# pmon_oled.net
KiCad netlist of a schematic drawn in EAGLE
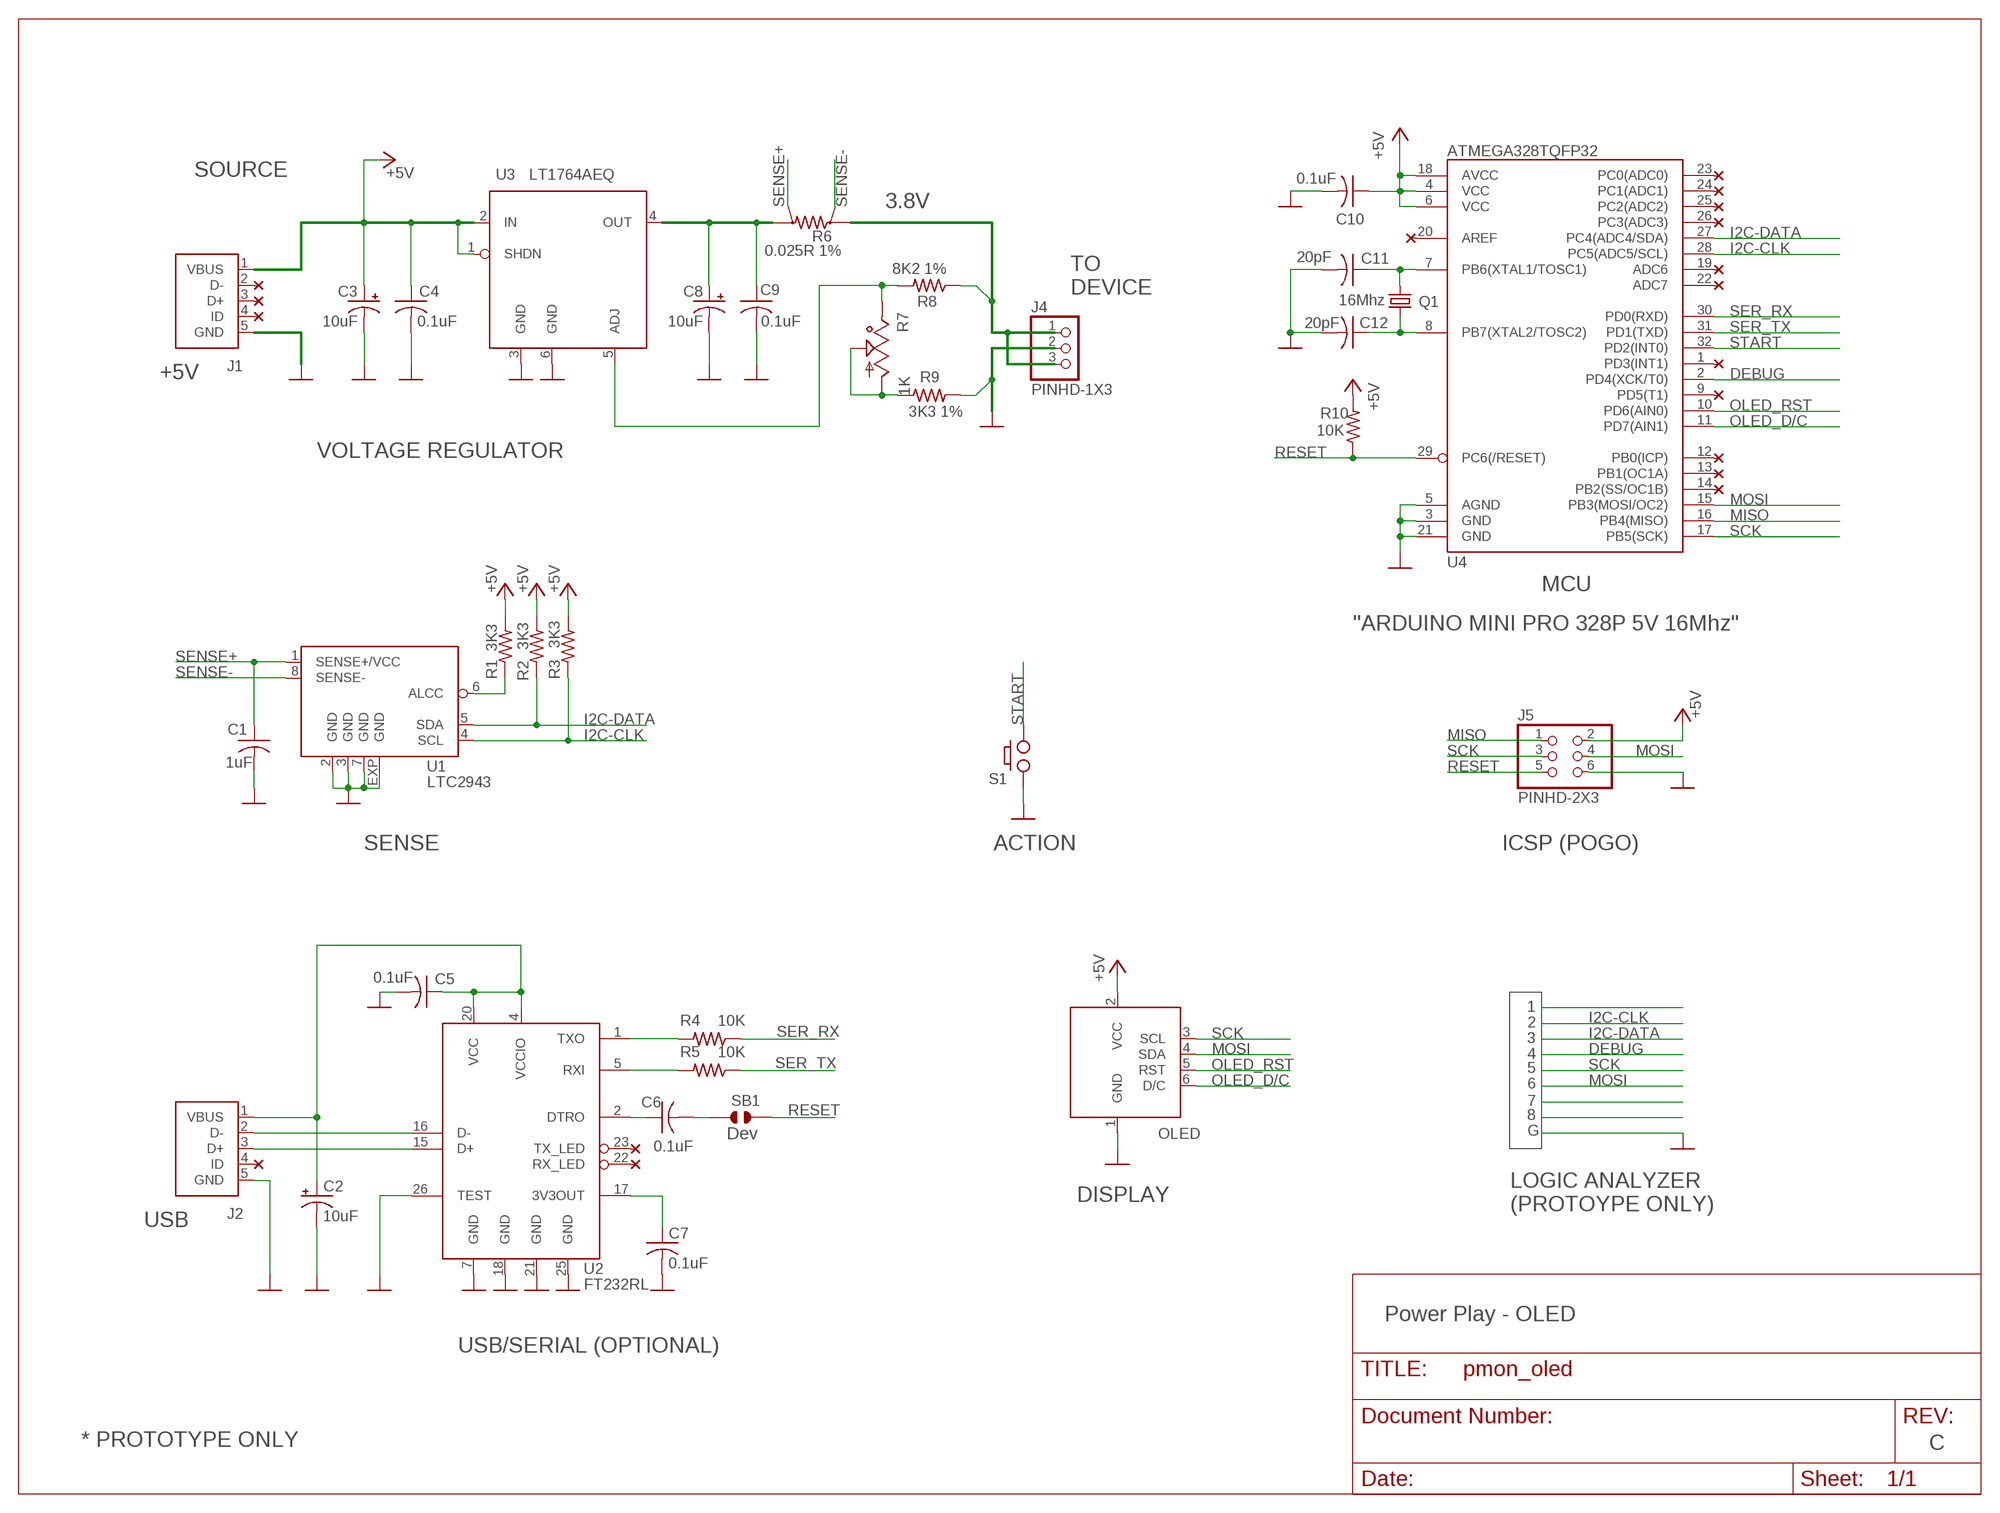
[diagram p0: schematic, sheet 1]

(export (version "E")
  (design (tool "Eeschema 10.0.6"))
  (components
    (comp (ref "C1")
      (value "1uF")
      (footprint "eagle-import:C0603")
      (libsource (lib "eagle-import") (part "CAP-C0603"))
    )
    (comp (ref "C2")
      (value "10uF")
      (footprint "eagle-import:A_3216-18R")
      (libsource (lib "eagle-import") (part "CPOL-USA/3216-18R"))
    )
    (comp (ref "C3")
      (value "10uF")
      (footprint "eagle-import:A_3216-18R")
      (libsource (lib "eagle-import") (part "CPOL-USA/3216-18R"))
    )
    (comp (ref "C4")
      (value "0.1uF")
      (footprint "eagle-import:C0603")
      (libsource (lib "eagle-import") (part "CAP-C0603"))
    )
    (comp (ref "C5")
      (value "0.1uF")
      (footprint "eagle-import:C0603")
      (libsource (lib "eagle-import") (part "CAP-C0603"))
    )
    (comp (ref "C6")
      (value "0.1uF")
      (footprint "eagle-import:C0603")
      (libsource (lib "eagle-import") (part "CAP-C0603"))
    )
    (comp (ref "C7")
      (value "0.1uF")
      (footprint "eagle-import:C0603")
      (libsource (lib "eagle-import") (part "CAP-C0603"))
    )
    (comp (ref "C8")
      (value "10uF")
      (footprint "eagle-import:A_3216-18R")
      (libsource (lib "eagle-import") (part "CPOL-USA/3216-18R"))
    )
    (comp (ref "C9")
      (value "0.1uF")
      (footprint "eagle-import:C0603")
      (libsource (lib "eagle-import") (part "CAP-C0603"))
    )
    (comp (ref "C10")
      (value "0.1uF")
      (footprint "eagle-import:C0603")
      (libsource (lib "eagle-import") (part "CAP-C0603"))
    )
    (comp (ref "C11")
      (value "20pF")
      (footprint "eagle-import:C0603")
      (libsource (lib "eagle-import") (part "CAP-C0603"))
    )
    (comp (ref "C12")
      (value "20pF")
      (footprint "eagle-import:C0603")
      (libsource (lib "eagle-import") (part "CAP-C0603"))
    )
    (comp (ref "J1")
      (value "USB")
      (footprint "eagle-import:USB-MICRO-ZX62RD-AB-5P8")
      (libsource (lib "eagle-import") (part "USB"))
    )
    (comp (ref "J2")
      (value "USB")
      (footprint "eagle-import:USB-MICRO-ZX62RD-AB-5P8")
      (libsource (lib "eagle-import") (part "USB"))
    )
    (comp (ref "J4")
      (value "PINHD-1X3")
      (footprint "eagle-import:1X03")
      (libsource (lib "eagle-import") (part "PINHD-1X3"))
    )
    (comp (ref "J5")
      (value "PINHD-2X3")
      (footprint "eagle-import:2X03")
      (libsource (lib "eagle-import") (part "PINHD-2X3"))
    )
    (comp (ref "OLED")
      (value "OLED")
      (footprint "eagle-import:OLED")
      (libsource (lib "eagle-import") (part "OLED"))
    )
    (comp (ref "Q1")
      (value "16Mhz")
      (footprint "eagle-import:CRYSTAL-CTS406")
      (libsource (lib "eagle-import") (part "CRYSTALCTS406"))
    )
    (comp (ref "R1")
      (value "3K3")
      (footprint "eagle-import:R0603")
      (libsource (lib "eagle-import") (part "RES-R0603"))
    )
    (comp (ref "R2")
      (value "3K3")
      (footprint "eagle-import:R0603")
      (libsource (lib "eagle-import") (part "RES-R0603"))
    )
    (comp (ref "R3")
      (value "3K3")
      (footprint "eagle-import:R0603")
      (libsource (lib "eagle-import") (part "RES-R0603"))
    )
    (comp (ref "R4")
      (value "10K")
      (footprint "eagle-import:R0603")
      (libsource (lib "eagle-import") (part "RES-R0603"))
    )
    (comp (ref "R5")
      (value "10K")
      (footprint "eagle-import:R0603")
      (libsource (lib "eagle-import") (part "RES-R0603"))
    )
    (comp (ref "R6")
      (value "0.025R 1%")
      (footprint "eagle-import:KELVIN-6432")
      (libsource (lib "eagle-import") (part "RES-SHUNT-6432"))
    )
    (comp (ref "R7")
      (value "1K")
      (footprint "eagle-import:TRIM-POT_SM-42_43A")
      (libsource (lib "eagle-import") (part "TRIM_US-SM-42/43A"))
    )
    (comp (ref "R8")
      (value "8K2 1%")
      (footprint "eagle-import:R0603")
      (libsource (lib "eagle-import") (part "RES-R0603"))
    )
    (comp (ref "R9")
      (value "3K3 1%")
      (footprint "eagle-import:R0603")
      (libsource (lib "eagle-import") (part "RES-R0603"))
    )
    (comp (ref "R10")
      (value "10K")
      (footprint "eagle-import:R0603")
      (libsource (lib "eagle-import") (part "RES-R0603"))
    )
    (comp (ref "S1")
      (value "PUSH_BUTTON")
      (footprint "eagle-import:TLE1105")
      (libsource (lib "eagle-import") (part "PUSH_BUTTON"))
    )
    (comp (ref "SB1")
      (value "JUMPER_SOLDER_1X2")
      (footprint "eagle-import:JUMPER_SOLDER_1X2")
      (libsource (lib "eagle-import") (part "JUMPER_SOLDER_1X2"))
    )
    (comp (ref "U1")
      (value "LTC2943")
      (footprint "eagle-import:DFN8-3X3")
      (libsource (lib "eagle-import") (part "LTC2943"))
    )
    (comp (ref "U2")
      (value "FT232RL")
      (footprint "eagle-import:SSOP28DB")
      (libsource (lib "eagle-import") (part "FT232RL"))
    )
    (comp (ref "U3")
      (value "LT1764AEQ")
      (footprint "eagle-import:TO263-5")
      (libsource (lib "eagle-import") (part "LTE1764"))
    )
    (comp (ref "U4")
      (value "ATMEGA328TQFP32")
      (footprint "eagle-import:TQFP32-08")
      (libsource (lib "eagle-import") (part "ATMEGA328TQFP32"))
    )
  )
  (nets
    (net (code "1") (name "+5V") (class "Default")
      (node (ref "C10") (pin "1") (pinfunction "1_1") (pintype "passive"))
      (node (ref "C3") (pin "+") (pinfunction "+_+") (pintype "passive"))
      (node (ref "C4") (pin "1") (pinfunction "1_1") (pintype "passive"))
      (node (ref "J1") (pin "1") (pinfunction "VBUS_1") (pintype "bidirectional"))
      (node (ref "J5") (pin "2") (pinfunction "2_2") (pintype "passive"))
      (node (ref "OLED") (pin "2") (pinfunction "VCC_2") (pintype "power_in"))
      (node (ref "R1") (pin "2") (pinfunction "2_2") (pintype "passive"))
      (node (ref "R10") (pin "2") (pinfunction "2_2") (pintype "passive"))
      (node (ref "R2") (pin "2") (pinfunction "2_2") (pintype "passive"))
      (node (ref "R3") (pin "2") (pinfunction "2_2") (pintype "passive"))
      (node (ref "U3") (pin "1") (pinfunction "SHDN_1") (pintype "bidirectional"))
      (node (ref "U3") (pin "2") (pinfunction "IN_2") (pintype "bidirectional"))
      (node (ref "U4") (pin "18") (pinfunction "AVCC_18") (pintype "power_in"))
      (node (ref "U4") (pin "4") (pinfunction "VCC_4") (pintype "power_in"))
      (node (ref "U4") (pin "6") (pinfunction "VCC_6") (pintype "power_in"))
    )
    (net (code "2") (name "/AREF") (class "Default")
      (node (ref "U4") (pin "20") (pinfunction "AREF_20") (pintype "power_in"))
    )
    (net (code "3") (name "/DEBUG") (class "Default")
      (node (ref "U4") (pin "2") (pinfunction "PD4(XCK/T0)_2") (pintype "bidirectional"))
    )
    (net (code "4") (name "/I2C-CLK") (class "Default")
      (node (ref "R3") (pin "1") (pinfunction "1_1") (pintype "passive"))
      (node (ref "U1") (pin "4") (pinfunction "SCL_4") (pintype "input"))
      (node (ref "U4") (pin "28") (pinfunction "PC5(ADC5/SCL)_28") (pintype "bidirectional"))
    )
    (net (code "5") (name "/I2C-DATA") (class "Default")
      (node (ref "R2") (pin "1") (pinfunction "1_1") (pintype "passive"))
      (node (ref "U1") (pin "5") (pinfunction "SDA_5") (pintype "bidirectional"))
      (node (ref "U4") (pin "27") (pinfunction "PC4(ADC4/SDA)_27") (pintype "bidirectional"))
    )
    (net (code "6") (name "/MISO") (class "Default")
      (node (ref "J5") (pin "1") (pinfunction "1_1") (pintype "passive"))
      (node (ref "U4") (pin "16") (pinfunction "PB4(MISO)_16") (pintype "bidirectional"))
    )
    (net (code "7") (name "/MOSI") (class "Default")
      (node (ref "J5") (pin "4") (pinfunction "4_4") (pintype "passive"))
      (node (ref "OLED") (pin "4") (pinfunction "SDA_4") (pintype "input"))
      (node (ref "U4") (pin "15") (pinfunction "PB3(MOSI/OC2)_15") (pintype "bidirectional"))
    )
    (net (code "8") (name "/OLED_D{slash}C") (class "Default")
      (node (ref "OLED") (pin "6") (pinfunction "D/C_6") (pintype "input"))
      (node (ref "U4") (pin "11") (pinfunction "PD7(AIN1)_11") (pintype "bidirectional"))
    )
    (net (code "9") (name "/OLED_RST") (class "Default")
      (node (ref "OLED") (pin "5") (pinfunction "RST_5") (pintype "input"))
      (node (ref "U4") (pin "10") (pinfunction "PD6(AIN0)_10") (pintype "bidirectional"))
    )
    (net (code "10") (name "/RESET") (class "Default")
      (node (ref "J5") (pin "5") (pinfunction "5_5") (pintype "passive"))
      (node (ref "R10") (pin "1") (pinfunction "1_1") (pintype "passive"))
      (node (ref "SB1") (pin "2") (pinfunction "2_2") (pintype "passive"))
      (node (ref "U4") (pin "29") (pinfunction "PC6(/RESET)_29") (pintype "bidirectional"))
    )
    (net (code "11") (name "/SCK") (class "Default")
      (node (ref "J5") (pin "3") (pinfunction "3_3") (pintype "passive"))
      (node (ref "OLED") (pin "3") (pinfunction "SCL_3") (pintype "input"))
      (node (ref "U4") (pin "17") (pinfunction "PB5(SCK)_17") (pintype "bidirectional"))
    )
    (net (code "12") (name "/SENSE+") (class "Default")
      (node (ref "C1") (pin "1") (pinfunction "1_1") (pintype "passive"))
      (node (ref "R6") (pin "V2") (pinfunction "V2_V2") (pintype "passive"))
      (node (ref "U1") (pin "1") (pinfunction "SENSE+/VCC_1") (pintype "passive"))
    )
    (net (code "13") (name "/SENSE-") (class "Default")
      (node (ref "R6") (pin "V1") (pinfunction "V1_V1") (pintype "passive"))
      (node (ref "U1") (pin "8") (pinfunction "SENSE-_8") (pintype "passive"))
    )
    (net (code "14") (name "/SER_RX") (class "Default")
      (node (ref "R4") (pin "1") (pinfunction "1_1") (pintype "passive"))
      (node (ref "U4") (pin "30") (pinfunction "PD0(RXD)_30") (pintype "bidirectional"))
    )
    (net (code "15") (name "/SER_TX") (class "Default")
      (node (ref "R5") (pin "1") (pinfunction "1_1") (pintype "passive"))
      (node (ref "U4") (pin "31") (pinfunction "PD1(TXD)_31") (pintype "bidirectional"))
    )
    (net (code "16") (name "/START") (class "Default")
      (node (ref "S1") (pin "B") (pinfunction "2_B") (pintype "passive"))
      (node (ref "U4") (pin "32") (pinfunction "PD2(INT0)_32") (pintype "bidirectional"))
    )
    (net (code "17") (name "GND") (class "Default")
      (node (ref "C1") (pin "2") (pinfunction "2_2") (pintype "passive"))
      (node (ref "C10") (pin "2") (pinfunction "2_2") (pintype "passive"))
      (node (ref "C11") (pin "2") (pinfunction "2_2") (pintype "passive"))
      (node (ref "C12") (pin "2") (pinfunction "2_2") (pintype "passive"))
      (node (ref "C2") (pin "-") (pinfunction "-_-") (pintype "passive"))
      (node (ref "C3") (pin "-") (pinfunction "-_-") (pintype "passive"))
      (node (ref "C4") (pin "2") (pinfunction "2_2") (pintype "passive"))
      (node (ref "C5") (pin "2") (pinfunction "2_2") (pintype "passive"))
      (node (ref "C7") (pin "2") (pinfunction "2_2") (pintype "passive"))
      (node (ref "C8") (pin "-") (pinfunction "-_-") (pintype "passive"))
      (node (ref "C9") (pin "2") (pinfunction "2_2") (pintype "passive"))
      (node (ref "J1") (pin "5") (pinfunction "GND_5") (pintype "bidirectional"))
      (node (ref "J2") (pin "5") (pinfunction "GND_5") (pintype "bidirectional"))
      (node (ref "J4") (pin "2") (pinfunction "2_2") (pintype "passive"))
      (node (ref "J5") (pin "6") (pinfunction "6_6") (pintype "passive"))
      (node (ref "OLED") (pin "1") (pinfunction "GND_1") (pintype "power_in"))
      (node (ref "R9") (pin "2") (pinfunction "2_2") (pintype "passive"))
      (node (ref "S1") (pin "A") (pinfunction "1_A") (pintype "passive"))
      (node (ref "U1") (pin "2") (pinfunction "GND_2") (pintype "power_in"))
      (node (ref "U1") (pin "3") (pinfunction "GND_3") (pintype "power_in"))
      (node (ref "U1") (pin "7") (pinfunction "GND_7") (pintype "power_in"))
      (node (ref "U1") (pin "EXP") (pinfunction "GND_EXP") (pintype "power_in"))
      (node (ref "U2") (pin "18") (pinfunction "GND_18") (pintype "power_in"))
      (node (ref "U2") (pin "21") (pinfunction "GND_21") (pintype "power_in"))
      (node (ref "U2") (pin "25") (pinfunction "GND_25") (pintype "power_in"))
      (node (ref "U2") (pin "26") (pinfunction "TEST_26") (pintype "input"))
      (node (ref "U2") (pin "7") (pinfunction "GND_7") (pintype "power_in"))
      (node (ref "U3") (pin "3") (pinfunction "GND_3") (pintype "bidirectional"))
      (node (ref "U3") (pin "6") (pinfunction "GND_6") (pintype "bidirectional"))
      (node (ref "U4") (pin "21") (pinfunction "GND_21") (pintype "power_in"))
      (node (ref "U4") (pin "3") (pinfunction "GND_3") (pintype "power_in"))
      (node (ref "U4") (pin "5") (pinfunction "AGND_5") (pintype "power_in"))
    )
    (net (code "18") (name "Net-(C6-Pad2)") (class "Default")
      (node (ref "C6") (pin "2") (pinfunction "2_2") (pintype "passive"))
      (node (ref "SB1") (pin "1") (pinfunction "1_1") (pintype "passive"))
    )
    (net (code "19") (name "Net-(J2-D+)") (class "Default")
      (node (ref "J2") (pin "3") (pinfunction "D+_3") (pintype "bidirectional"))
      (node (ref "U2") (pin "15") (pinfunction "D+_15") (pintype "passive"))
    )
    (net (code "20") (name "Net-(J2-D-)") (class "Default")
      (node (ref "J2") (pin "2") (pinfunction "D-_2") (pintype "bidirectional"))
      (node (ref "U2") (pin "16") (pinfunction "D-_16") (pintype "passive"))
    )
    (net (code "21") (name "Net-(J2-VBUS)") (class "Default")
      (node (ref "C2") (pin "+") (pinfunction "+_+") (pintype "passive"))
      (node (ref "C5") (pin "1") (pinfunction "1_1") (pintype "passive"))
      (node (ref "J2") (pin "1") (pinfunction "VBUS_1") (pintype "bidirectional"))
      (node (ref "U2") (pin "20") (pinfunction "VCC_20") (pintype "power_in"))
      (node (ref "U2") (pin "4") (pinfunction "VCCIO_4") (pintype "power_in"))
    )
    (net (code "22") (name "Net-(J4-Pad1)") (class "Default")
      (node (ref "J4") (pin "1") (pinfunction "1_1") (pintype "passive"))
      (node (ref "J4") (pin "3") (pinfunction "3_3") (pintype "passive"))
      (node (ref "R6") (pin "I1") (pinfunction "I1_I1") (pintype "passive"))
      (node (ref "R8") (pin "1") (pinfunction "1_1") (pintype "passive"))
    )
    (net (code "23") (name "Net-(Q1-2)") (class "Default")
      (node (ref "C12") (pin "1") (pinfunction "1_1") (pintype "passive"))
      (node (ref "Q1") (pin "3") (pinfunction "2_3") (pintype "passive"))
      (node (ref "U4") (pin "8") (pinfunction "PB7(XTAL2/TOSC2)_8") (pintype "bidirectional"))
    )
    (net (code "24") (name "Net-(R7-Pad1)") (class "Default")
      (node (ref "R7") (pin "1") (pinfunction "1_1") (pintype "passive"))
      (node (ref "R7") (pin "2") (pinfunction "2_2") (pintype "passive"))
      (node (ref "R9") (pin "1") (pinfunction "1_1") (pintype "passive"))
    )
    (net (code "25") (name "Net-(U1-ALCC)") (class "Default")
      (node (ref "R1") (pin "1") (pinfunction "1_1") (pintype "passive"))
      (node (ref "U1") (pin "6") (pinfunction "ALCC_6") (pintype "open_collector"))
    )
    (net (code "26") (name "Net-(U2-3V3OUT)") (class "Default")
      (node (ref "C7") (pin "1") (pinfunction "1_1") (pintype "passive"))
      (node (ref "U2") (pin "17") (pinfunction "3V3OUT_17") (pintype "power_in"))
    )
    (net (code "27") (name "Net-(U2-DTRO)") (class "Default")
      (node (ref "C6") (pin "1") (pinfunction "1_1") (pintype "passive"))
      (node (ref "U2") (pin "2") (pinfunction "DTRO_2") (pintype "output"))
    )
    (net (code "28") (name "Net-(U2-RXI)") (class "Default")
      (node (ref "R5") (pin "2") (pinfunction "2_2") (pintype "passive"))
      (node (ref "U2") (pin "5") (pinfunction "RXI_5") (pintype "input"))
    )
    (net (code "29") (name "Net-(U2-TXO)") (class "Default")
      (node (ref "R4") (pin "2") (pinfunction "2_2") (pintype "passive"))
      (node (ref "U2") (pin "1") (pinfunction "TXO_1") (pintype "output"))
    )
    (net (code "30") (name "Net-(U3-ADJ)") (class "Default")
      (node (ref "R7") (pin "3") (pinfunction "3_3") (pintype "passive"))
      (node (ref "R8") (pin "2") (pinfunction "2_2") (pintype "passive"))
      (node (ref "U3") (pin "5") (pinfunction "ADJ_5") (pintype "bidirectional"))
    )
    (net (code "31") (name "Net-(U3-OUT)") (class "Default")
      (node (ref "C8") (pin "+") (pinfunction "+_+") (pintype "passive"))
      (node (ref "C9") (pin "1") (pinfunction "1_1") (pintype "passive"))
      (node (ref "R6") (pin "I2") (pinfunction "I2_I2") (pintype "passive"))
      (node (ref "U3") (pin "4") (pinfunction "OUT_4") (pintype "bidirectional"))
    )
    (net (code "32") (name "Net-(U4-PB6(XTAL1{slash}TOSC1))") (class "Default")
      (node (ref "C11") (pin "1") (pinfunction "1_1") (pintype "passive"))
      (node (ref "Q1") (pin "1") (pinfunction "1_1") (pintype "passive"))
      (node (ref "U4") (pin "7") (pinfunction "PB6(XTAL1/TOSC1)_7") (pintype "bidirectional"))
    )
    (net (code "33") (name "unconnected-(J1-D+-Pad3)") (class "Default")
      (node (ref "J1") (pin "3") (pinfunction "D+_3") (pintype "bidirectional"))
    )
    (net (code "34") (name "unconnected-(J1-D--Pad2)") (class "Default")
      (node (ref "J1") (pin "2") (pinfunction "D-_2") (pintype "bidirectional"))
    )
    (net (code "35") (name "unconnected-(J1-ID-Pad4)") (class "Default")
      (node (ref "J1") (pin "4") (pinfunction "ID_4") (pintype "bidirectional"))
    )
    (net (code "36") (name "unconnected-(J2-ID-Pad4)") (class "Default")
      (node (ref "J2") (pin "4") (pinfunction "ID_4") (pintype "bidirectional"))
    )
    (net (code "37") (name "unconnected-(U2-RX_LED-Pad22)") (class "Default")
      (node (ref "U2") (pin "22") (pinfunction "RX_LED_22") (pintype "output"))
    )
    (net (code "38") (name "unconnected-(U2-TX_LED-Pad23)") (class "Default")
      (node (ref "U2") (pin "23") (pinfunction "TX_LED_23") (pintype "output"))
    )
    (net (code "39") (name "unconnected-(U4-ADC6-Pad19)") (class "Default")
      (node (ref "U4") (pin "19") (pinfunction "ADC6_19") (pintype "bidirectional"))
    )
    (net (code "40") (name "unconnected-(U4-ADC7-Pad22)") (class "Default")
      (node (ref "U4") (pin "22") (pinfunction "ADC7_22") (pintype "bidirectional"))
    )
    (net (code "41") (name "unconnected-(U4-PB0(ICP)-Pad12)") (class "Default")
      (node (ref "U4") (pin "12") (pinfunction "PB0(ICP)_12") (pintype "bidirectional"))
    )
    (net (code "42") (name "unconnected-(U4-PB1(OC1A)-Pad13)") (class "Default")
      (node (ref "U4") (pin "13") (pinfunction "PB1(OC1A)_13") (pintype "bidirectional"))
    )
    (net (code "43") (name "unconnected-(U4-PB2(SS{slash}OC1B)-Pad14)") (class "Default")
      (node (ref "U4") (pin "14") (pinfunction "PB2(SS/OC1B)_14") (pintype "bidirectional"))
    )
    (net (code "44") (name "unconnected-(U4-PC0(ADC0)-Pad23)") (class "Default")
      (node (ref "U4") (pin "23") (pinfunction "PC0(ADC0)_23") (pintype "bidirectional"))
    )
    (net (code "45") (name "unconnected-(U4-PC1(ADC1)-Pad24)") (class "Default")
      (node (ref "U4") (pin "24") (pinfunction "PC1(ADC1)_24") (pintype "bidirectional"))
    )
    (net (code "46") (name "unconnected-(U4-PC2(ADC2)-Pad25)") (class "Default")
      (node (ref "U4") (pin "25") (pinfunction "PC2(ADC2)_25") (pintype "bidirectional"))
    )
    (net (code "47") (name "unconnected-(U4-PC3(ADC3)-Pad26)") (class "Default")
      (node (ref "U4") (pin "26") (pinfunction "PC3(ADC3)_26") (pintype "bidirectional"))
    )
    (net (code "48") (name "unconnected-(U4-PD3(INT1)-Pad1)") (class "Default")
      (node (ref "U4") (pin "1") (pinfunction "PD3(INT1)_1") (pintype "bidirectional"))
    )
    (net (code "49") (name "unconnected-(U4-PD5(T1)-Pad9)") (class "Default")
      (node (ref "U4") (pin "9") (pinfunction "PD5(T1)_9") (pintype "bidirectional"))
    )
  )
)
